# medusa-ai-audio.net
KiCad netlist of a schematic drawn in Altium Designer
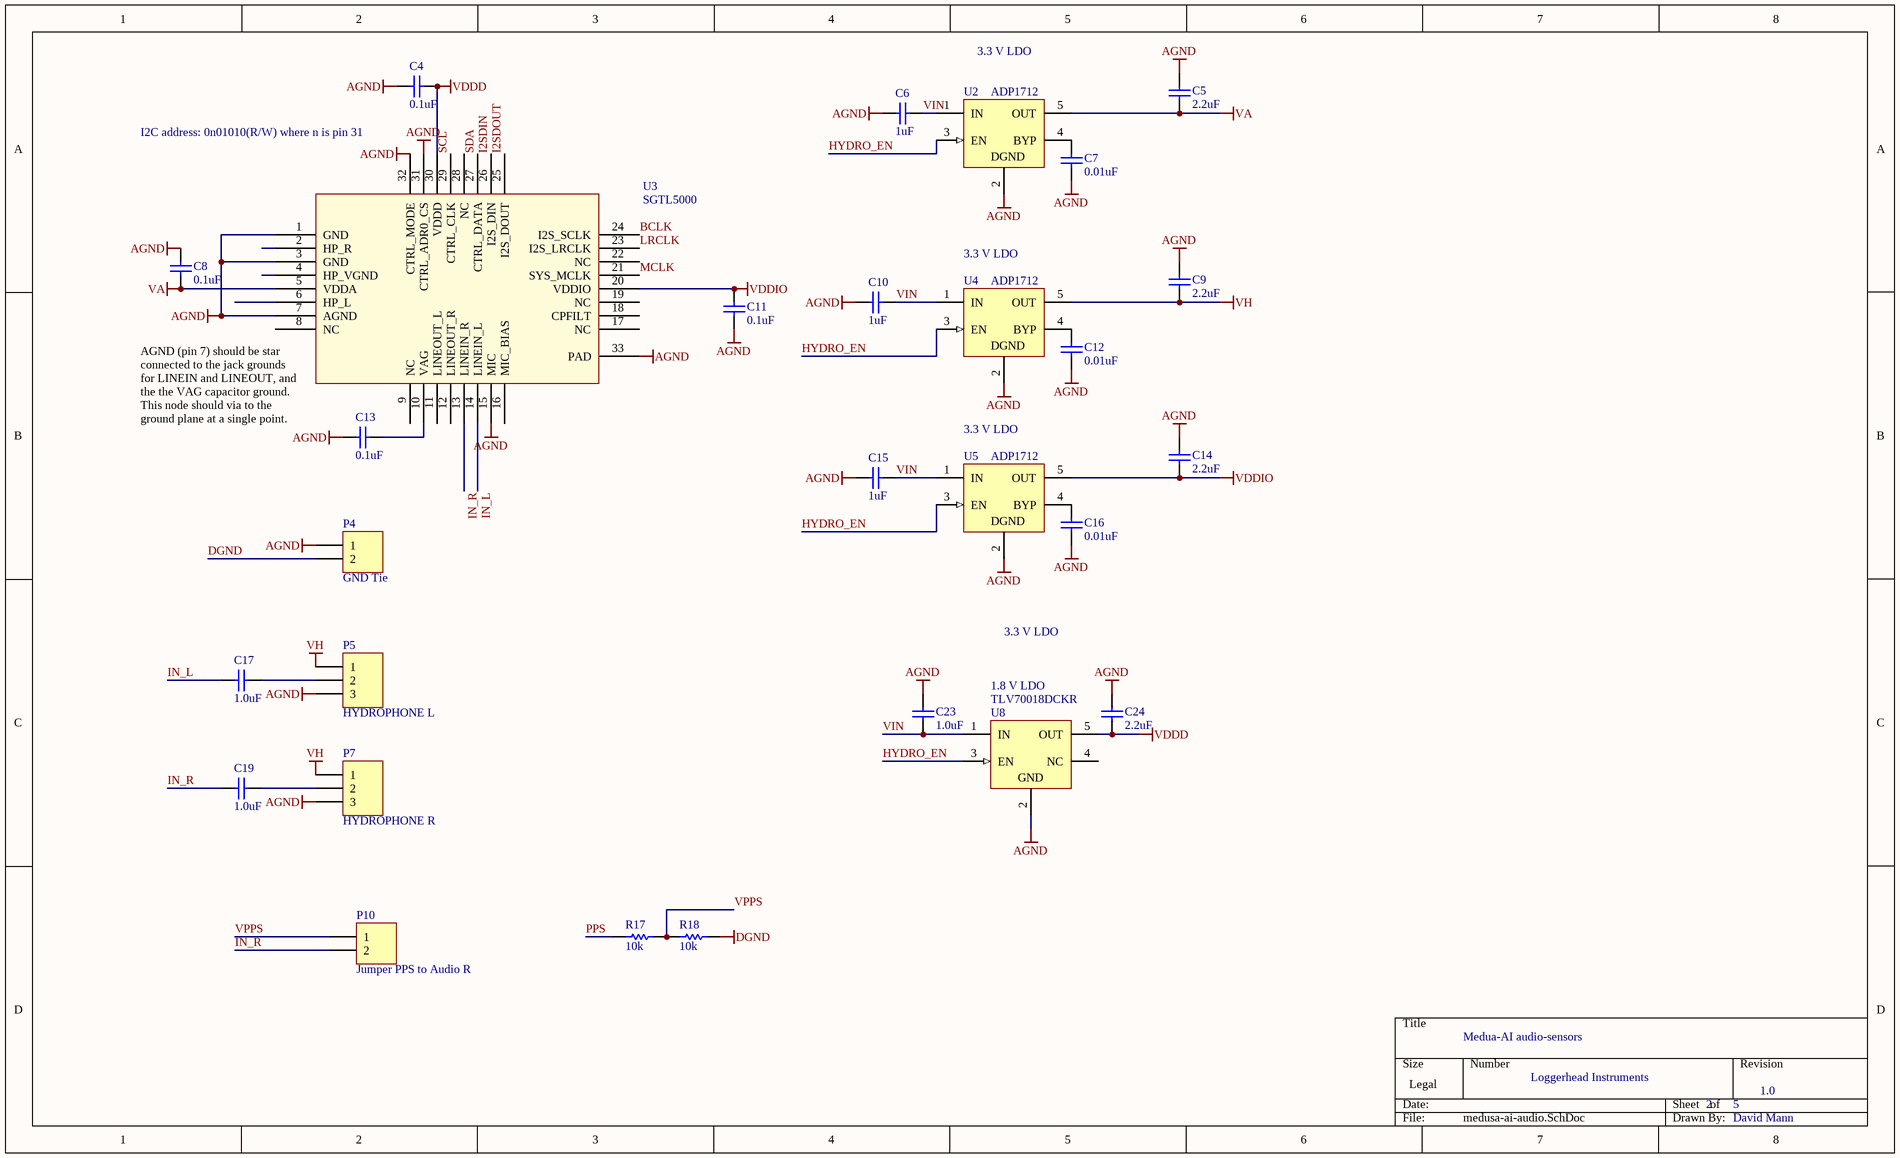
[diagram p0: medusa-ai-audio.SchDoc]

(export (version "E")
  (design (tool "Eeschema 10.0.6"))
  (components
    (comp (ref "C4")
      (value "0.1uF")
      (footprint "0402")
      (description "Ceramic Chip Capacitor - Standard")
      (fields (field (name "PUBLISHER") "Altium Limited"))
      (libsource (lib "KEMET Chip Capacitor") (part "C0402"))
    )
    (comp (ref "C5")
      (value "2.2uF")
      (footprint "0402")
      (description "Ceramic Chip Capacitor - Standard")
      (fields (field (name "PUBLISHER") "Altium Limited"))
      (libsource (lib "KEMET Chip Capacitor") (part "C0402"))
    )
    (comp (ref "C6")
      (value "1uF")
      (footprint "0402")
      (description "Ceramic Chip Capacitor - Standard")
      (fields (field (name "PUBLISHER") "Altium Limited"))
      (libsource (lib "KEMET Chip Capacitor") (part "C0402"))
    )
    (comp (ref "C7")
      (value "0.01uF")
      (footprint "0402")
      (description "Ceramic Chip Capacitor - Standard")
      (fields (field (name "PUBLISHER") "Altium Limited"))
      (libsource (lib "KEMET Chip Capacitor") (part "C0402"))
    )
    (comp (ref "C8")
      (value "0.1uF")
      (footprint "0402")
      (description "Ceramic Chip Capacitor - Standard")
      (fields (field (name "PUBLISHER") "Altium Limited"))
      (libsource (lib "KEMET Chip Capacitor") (part "C0402"))
    )
    (comp (ref "C9")
      (value "2.2uF")
      (footprint "0402")
      (description "Ceramic Chip Capacitor - Standard")
      (fields (field (name "PUBLISHER") "Altium Limited"))
      (libsource (lib "KEMET Chip Capacitor") (part "C0402"))
    )
    (comp (ref "C10")
      (value "1uF")
      (footprint "0402")
      (description "Ceramic Chip Capacitor - Standard")
      (fields (field (name "PUBLISHER") "Altium Limited"))
      (libsource (lib "KEMET Chip Capacitor") (part "C0402"))
    )
    (comp (ref "C11")
      (value "0.1uF")
      (footprint "0402")
      (description "Ceramic Chip Capacitor - Standard")
      (fields (field (name "PUBLISHER") "Altium Limited"))
      (libsource (lib "KEMET Chip Capacitor") (part "C0402"))
    )
    (comp (ref "C12")
      (value "0.01uF")
      (footprint "0402")
      (description "Ceramic Chip Capacitor - Standard")
      (fields (field (name "PUBLISHER") "Altium Limited"))
      (libsource (lib "KEMET Chip Capacitor") (part "C0402"))
    )
    (comp (ref "C13")
      (value "0.1uF")
      (footprint "0402")
      (description "Ceramic Chip Capacitor - Standard")
      (fields (field (name "PUBLISHER") "Altium Limited"))
      (libsource (lib "KEMET Chip Capacitor") (part "C0402"))
    )
    (comp (ref "C14")
      (value "2.2uF")
      (footprint "0402")
      (description "Ceramic Chip Capacitor - Standard")
      (fields (field (name "PUBLISHER") "Altium Limited"))
      (libsource (lib "KEMET Chip Capacitor") (part "C0402"))
    )
    (comp (ref "C15")
      (value "1uF")
      (footprint "0402")
      (description "Ceramic Chip Capacitor - Standard")
      (fields (field (name "PUBLISHER") "Altium Limited"))
      (libsource (lib "KEMET Chip Capacitor") (part "C0402"))
    )
    (comp (ref "C16")
      (value "0.01uF")
      (footprint "0402")
      (description "Ceramic Chip Capacitor - Standard")
      (fields (field (name "PUBLISHER") "Altium Limited"))
      (libsource (lib "KEMET Chip Capacitor") (part "C0402"))
    )
    (comp (ref "C17")
      (value "1.0uF")
      (footprint "0402")
      (description "Ceramic Chip Capacitor - Standard")
      (fields (field (name "PUBLISHER") "Altium Limited"))
      (libsource (lib "KEMET Chip Capacitor") (part "C0402"))
    )
    (comp (ref "C19")
      (value "1.0uF")
      (footprint "0402")
      (description "Ceramic Chip Capacitor - Standard")
      (fields (field (name "PUBLISHER") "Altium Limited"))
      (libsource (lib "KEMET Chip Capacitor") (part "C0402"))
    )
    (comp (ref "C23")
      (value "1.0uF")
      (footprint "0402")
      (description "Ceramic Chip Capacitor - Standard")
      (fields (field (name "PUBLISHER") "Altium Limited"))
      (libsource (lib "KEMET Chip Capacitor") (part "C0402"))
    )
    (comp (ref "C24")
      (value "2.2uF")
      (footprint "0402")
      (description "Ceramic Chip Capacitor - Standard")
      (fields (field (name "PUBLISHER") "Altium Limited"))
      (libsource (lib "KEMET Chip Capacitor") (part "C0402"))
    )
    (comp (ref "P4")
      (value "GND Tie")
      (footprint "HDR1X2")
      (description "Header, 2-Pin")
      (fields (field (name "PUBLISHER") "Altium Limited"))
      (libsource (lib "Miscellaneous Connectors") (part "Header 2"))
    )
    (comp (ref "P5")
      (value "HYDROPHONE L")
      (footprint "HDR1X3")
      (description "Header, 3-Pin")
      (fields (field (name "PUBLISHER") "Altium Limited"))
      (libsource (lib "Miscellaneous Connectors") (part "Header 3"))
    )
    (comp (ref "P7")
      (value "HYDROPHONE R")
      (footprint "HDR1X3")
      (description "Header, 3-Pin")
      (fields (field (name "PUBLISHER") "Altium Limited"))
      (libsource (lib "Miscellaneous Connectors") (part "Header 3"))
    )
    (comp (ref "P10")
      (value "Jumper PPS to Audio R")
      (footprint "HDR1X2")
      (description "Header, 2-Pin")
      (fields (field (name "PUBLISHER") "Altium Limited"))
      (libsource (lib "Miscellaneous Connectors") (part "Header 2"))
    )
    (comp (ref "R17")
      (value "10k")
      (footprint "3-0603")
      (fields (field (name "PUBLISHER") "Altium Limited"))
      (libsource (lib "Panasonic Resistor") (part "ERJ3RK"))
    )
    (comp (ref "R18")
      (value "10k")
      (footprint "3-0603")
      (fields (field (name "PUBLISHER") "Altium Limited"))
      (libsource (lib "Panasonic Resistor") (part "ERJ3RK"))
    )
    (comp (ref "U2")
      (value "ADP1712")
      (footprint "MF05A_N")
      (description "Micropower, 150mA Low-Noise Ultra Low-Dropout CMOS Voltage Regulator")
      (fields
        (field (name "PARTNUMBER") "LP3985IM5-3.3")
        (field (name "MANUFACTURER") "National Semiconductor")
        (field (name "PUBLISHER") "Altium Limited")
      )
      (libsource (lib "NSC LDO") (part "LP3985IM5-3.3"))
    )
    (comp (ref "U3") (value "SGTL5000") (footprint "QFN32") (libsource (lib "Loggerhead") (part "SGTL5000")))
    (comp (ref "U4")
      (value "ADP1712")
      (footprint "MF05A_N")
      (description "Micropower, 150mA Low-Noise Ultra Low-Dropout CMOS Voltage Regulator")
      (fields
        (field (name "PARTNUMBER") "LP3985IM5-3.3")
        (field (name "MANUFACTURER") "National Semiconductor")
        (field (name "PUBLISHER") "Altium Limited")
      )
      (libsource (lib "NSC LDO") (part "LP3985IM5-3.3"))
    )
    (comp (ref "U5")
      (value "ADP1712")
      (footprint "MF05A_N")
      (description "Micropower, 150mA Low-Noise Ultra Low-Dropout CMOS Voltage Regulator")
      (fields
        (field (name "PARTNUMBER") "LP3985IM5-3.3")
        (field (name "MANUFACTURER") "National Semiconductor")
        (field (name "PUBLISHER") "Altium Limited")
      )
      (libsource (lib "NSC LDO") (part "LP3985IM5-3.3"))
    )
    (comp (ref "U8")
      (value "TLV70018DCKR")
      (footprint "TI-DCK5_V")
      (fields (field (name "MANUFACTURER") "Texas Instruments"))
      (libsource (lib "TI Power Management Linear Regulator Single Channel LDO (0-350mA)") (part "TLV70018DCKR"))
    )
  )
  (nets
    (net (code "1") (name "/BCLK") (class "Default")
      (node (ref "U3") (pin "24") (pinfunction "I2S_SCLK_24") (pintype "passive"))
    )
    (net (code "2") (name "/HYDRO_EN") (class "Default")
      (node (ref "U2") (pin "3") (pinfunction "EN_3") (pintype "input"))
      (node (ref "U4") (pin "3") (pinfunction "EN_3") (pintype "input"))
      (node (ref "U5") (pin "3") (pinfunction "EN_3") (pintype "input"))
      (node (ref "U8") (pin "3") (pinfunction "EN_3") (pintype "input"))
    )
    (net (code "3") (name "/I2SDIN") (class "Default")
      (node (ref "U3") (pin "26") (pinfunction "I2S_DIN_26") (pintype "passive"))
    )
    (net (code "4") (name "/I2SDOUT") (class "Default")
      (node (ref "U3") (pin "25") (pinfunction "I2S_DOUT_25") (pintype "passive"))
    )
    (net (code "5") (name "/IN_L") (class "Default")
      (node (ref "C17") (pin "2") (pinfunction "2_2") (pintype "passive"))
      (node (ref "U3") (pin "14") (pinfunction "LINEIN_L_14") (pintype "passive"))
    )
    (net (code "6") (name "/IN_R") (class "Default")
      (node (ref "C19") (pin "2") (pinfunction "2_2") (pintype "passive"))
      (node (ref "P10") (pin "2") (pinfunction "2_2") (pintype "passive"))
      (node (ref "U3") (pin "13") (pinfunction "LINEIN_R_13") (pintype "passive"))
    )
    (net (code "7") (name "/LRCLK") (class "Default")
      (node (ref "U3") (pin "23") (pinfunction "I2S_LRCLK_23") (pintype "passive"))
    )
    (net (code "8") (name "/MCLK") (class "Default")
      (node (ref "U3") (pin "21") (pinfunction "SYS_MCLK_21") (pintype "passive"))
    )
    (net (code "9") (name "/PPS") (class "Default")
      (node (ref "R17") (pin "2") (pinfunction "2_2") (pintype "passive"))
    )
    (net (code "10") (name "/SCL") (class "Default")
      (node (ref "U3") (pin "29") (pinfunction "CTRL_CLK_29") (pintype "passive"))
    )
    (net (code "11") (name "/SDA") (class "Default")
      (node (ref "U3") (pin "27") (pinfunction "CTRL_DATA_27") (pintype "passive"))
    )
    (net (code "12") (name "/VIN") (class "Default")
      (node (ref "C10") (pin "1") (pinfunction "1_1") (pintype "passive"))
      (node (ref "C15") (pin "1") (pinfunction "1_1") (pintype "passive"))
      (node (ref "C23") (pin "1") (pinfunction "1_1") (pintype "passive"))
      (node (ref "C6") (pin "1") (pinfunction "1_1") (pintype "passive"))
      (node (ref "U2") (pin "1") (pinfunction "IN_1") (pintype "power_in"))
      (node (ref "U4") (pin "1") (pinfunction "IN_1") (pintype "power_in"))
      (node (ref "U5") (pin "1") (pinfunction "IN_1") (pintype "power_in"))
      (node (ref "U8") (pin "1") (pinfunction "IN_1") (pintype "power_in"))
    )
    (net (code "13") (name "/VPPS") (class "Default")
      (node (ref "P10") (pin "1") (pinfunction "1_1") (pintype "passive"))
      (node (ref "R17") (pin "1") (pinfunction "1_1") (pintype "passive"))
      (node (ref "R18") (pin "2") (pinfunction "2_2") (pintype "passive"))
    )
    (net (code "14") (name "AGND") (class "Default")
      (node (ref "C10") (pin "2") (pinfunction "2_2") (pintype "passive"))
      (node (ref "C11") (pin "2") (pinfunction "2_2") (pintype "passive"))
      (node (ref "C12") (pin "2") (pinfunction "2_2") (pintype "passive"))
      (node (ref "C13") (pin "2") (pinfunction "2_2") (pintype "passive"))
      (node (ref "C14") (pin "2") (pinfunction "2_2") (pintype "passive"))
      (node (ref "C15") (pin "2") (pinfunction "2_2") (pintype "passive"))
      (node (ref "C16") (pin "2") (pinfunction "2_2") (pintype "passive"))
      (node (ref "C23") (pin "2") (pinfunction "2_2") (pintype "passive"))
      (node (ref "C24") (pin "2") (pinfunction "2_2") (pintype "passive"))
      (node (ref "C4") (pin "2") (pinfunction "2_2") (pintype "passive"))
      (node (ref "C5") (pin "2") (pinfunction "2_2") (pintype "passive"))
      (node (ref "C6") (pin "2") (pinfunction "2_2") (pintype "passive"))
      (node (ref "C7") (pin "2") (pinfunction "2_2") (pintype "passive"))
      (node (ref "C8") (pin "2") (pinfunction "2_2") (pintype "passive"))
      (node (ref "C9") (pin "2") (pinfunction "2_2") (pintype "passive"))
      (node (ref "P4") (pin "1") (pinfunction "1_1") (pintype "passive"))
      (node (ref "P5") (pin "3") (pinfunction "3_3") (pintype "passive"))
      (node (ref "P7") (pin "3") (pinfunction "3_3") (pintype "passive"))
      (node (ref "U2") (pin "2") (pinfunction "GND_2") (pintype "power_in"))
      (node (ref "U3") (pin "1") (pinfunction "GND_1") (pintype "passive"))
      (node (ref "U3") (pin "15") (pinfunction "MIC_15") (pintype "passive"))
      (node (ref "U3") (pin "3") (pinfunction "GND_3") (pintype "passive"))
      (node (ref "U3") (pin "31") (pinfunction "CTRL_ADR0_CS_31") (pintype "passive"))
      (node (ref "U3") (pin "32") (pinfunction "CTRL_MODE_32") (pintype "passive"))
      (node (ref "U3") (pin "33") (pinfunction "PAD_33") (pintype "passive"))
      (node (ref "U3") (pin "7") (pinfunction "AGND_7") (pintype "passive"))
      (node (ref "U4") (pin "2") (pinfunction "GND_2") (pintype "power_in"))
      (node (ref "U5") (pin "2") (pinfunction "GND_2") (pintype "power_in"))
      (node (ref "U8") (pin "2") (pinfunction "GND_2") (pintype "power_in"))
    )
    (net (code "15") (name "DGND") (class "Default")
      (node (ref "P4") (pin "2") (pinfunction "2_2") (pintype "passive"))
      (node (ref "R18") (pin "1") (pinfunction "1_1") (pintype "passive"))
    )
    (net (code "16") (name "Net-(C17-Pad1)") (class "Default")
      (node (ref "C17") (pin "1") (pinfunction "1_1") (pintype "passive"))
      (node (ref "P5") (pin "2") (pinfunction "2_2") (pintype "passive"))
    )
    (net (code "17") (name "Net-(C19-Pad1)") (class "Default")
      (node (ref "C19") (pin "1") (pinfunction "1_1") (pintype "passive"))
      (node (ref "P7") (pin "2") (pinfunction "2_2") (pintype "passive"))
    )
    (net (code "18") (name "Net-(U2-BYP)") (class "Default")
      (node (ref "C7") (pin "1") (pinfunction "1_1") (pintype "passive"))
      (node (ref "U2") (pin "4") (pinfunction "BYP_4") (pintype "passive"))
    )
    (net (code "19") (name "Net-(U3-VAG)") (class "Default")
      (node (ref "C13") (pin "1") (pinfunction "1_1") (pintype "passive"))
      (node (ref "U3") (pin "10") (pinfunction "VAG_10") (pintype "passive"))
    )
    (net (code "20") (name "Net-(U4-BYP)") (class "Default")
      (node (ref "C12") (pin "1") (pinfunction "1_1") (pintype "passive"))
      (node (ref "U4") (pin "4") (pinfunction "BYP_4") (pintype "passive"))
    )
    (net (code "21") (name "Net-(U5-BYP)") (class "Default")
      (node (ref "C16") (pin "1") (pinfunction "1_1") (pintype "passive"))
      (node (ref "U5") (pin "4") (pinfunction "BYP_4") (pintype "passive"))
    )
    (net (code "22") (name "VA") (class "Default")
      (node (ref "C5") (pin "1") (pinfunction "1_1") (pintype "passive"))
      (node (ref "C8") (pin "1") (pinfunction "1_1") (pintype "passive"))
      (node (ref "U2") (pin "5") (pinfunction "OUT_5") (pintype "power_in"))
      (node (ref "U3") (pin "5") (pinfunction "VDDA_5") (pintype "passive"))
    )
    (net (code "23") (name "VDDD") (class "Default")
      (node (ref "C24") (pin "1") (pinfunction "1_1") (pintype "passive"))
      (node (ref "C4") (pin "1") (pinfunction "1_1") (pintype "passive"))
      (node (ref "U3") (pin "30") (pinfunction "VDDD_30") (pintype "passive"))
      (node (ref "U8") (pin "5") (pinfunction "OUT_5") (pintype "power_in"))
    )
    (net (code "24") (name "VDDIO") (class "Default")
      (node (ref "C11") (pin "1") (pinfunction "1_1") (pintype "passive"))
      (node (ref "C14") (pin "1") (pinfunction "1_1") (pintype "passive"))
      (node (ref "U3") (pin "20") (pinfunction "VDDIO_20") (pintype "passive"))
      (node (ref "U5") (pin "5") (pinfunction "OUT_5") (pintype "power_in"))
    )
    (net (code "25") (name "VH") (class "Default")
      (node (ref "C9") (pin "1") (pinfunction "1_1") (pintype "passive"))
      (node (ref "P5") (pin "1") (pinfunction "1_1") (pintype "passive"))
      (node (ref "P7") (pin "1") (pinfunction "1_1") (pintype "passive"))
      (node (ref "U4") (pin "5") (pinfunction "OUT_5") (pintype "power_in"))
    )
    (net (code "26") (name "unconnected-(U3-CPFILT-Pad18)") (class "Default")
      (node (ref "U3") (pin "18") (pinfunction "CPFILT_18") (pintype "passive"))
    )
    (net (code "27") (name "unconnected-(U3-HP_L-Pad6)") (class "Default")
      (node (ref "U3") (pin "6") (pinfunction "HP_L_6") (pintype "passive"))
    )
    (net (code "28") (name "unconnected-(U3-HP_R-Pad2)") (class "Default")
      (node (ref "U3") (pin "2") (pinfunction "HP_R_2") (pintype "passive"))
    )
    (net (code "29") (name "unconnected-(U3-HP_VGND-Pad4)") (class "Default")
      (node (ref "U3") (pin "4") (pinfunction "HP_VGND_4") (pintype "passive"))
    )
    (net (code "30") (name "unconnected-(U3-LINEOUT_L-Pad11)") (class "Default")
      (node (ref "U3") (pin "11") (pinfunction "LINEOUT_L_11") (pintype "passive"))
    )
    (net (code "31") (name "unconnected-(U3-LINEOUT_R-Pad12)") (class "Default")
      (node (ref "U3") (pin "12") (pinfunction "LINEOUT_R_12") (pintype "passive"))
    )
    (net (code "32") (name "unconnected-(U3-MIC_BIAS-Pad16)") (class "Default")
      (node (ref "U3") (pin "16") (pinfunction "MIC_BIAS_16") (pintype "passive"))
    )
    (net (code "33") (name "unconnected-(U3-NC-Pad8)") (class "Default")
      (node (ref "U3") (pin "8") (pinfunction "NC_8") (pintype "passive"))
    )
    (net (code "34") (name "unconnected-(U3-NC-Pad9)") (class "Default")
      (node (ref "U3") (pin "9") (pinfunction "NC_9") (pintype "passive"))
    )
    (net (code "35") (name "unconnected-(U3-NC-Pad17)") (class "Default")
      (node (ref "U3") (pin "17") (pinfunction "NC_17") (pintype "passive"))
    )
    (net (code "36") (name "unconnected-(U3-NC-Pad19)") (class "Default")
      (node (ref "U3") (pin "19") (pinfunction "NC_19") (pintype "passive"))
    )
    (net (code "37") (name "unconnected-(U3-NC-Pad22)") (class "Default")
      (node (ref "U3") (pin "22") (pinfunction "NC_22") (pintype "passive"))
    )
    (net (code "38") (name "unconnected-(U3-NC-Pad28)") (class "Default")
      (node (ref "U3") (pin "28") (pinfunction "NC_28") (pintype "passive"))
    )
    (net (code "39") (name "unconnected-(U8-NC-Pad4)") (class "Default")
      (node (ref "U8") (pin "4") (pinfunction "NC_4") (pintype "passive"))
    )
  )
)
